# Master.net
KiCad netlist of a schematic drawn in EAGLE
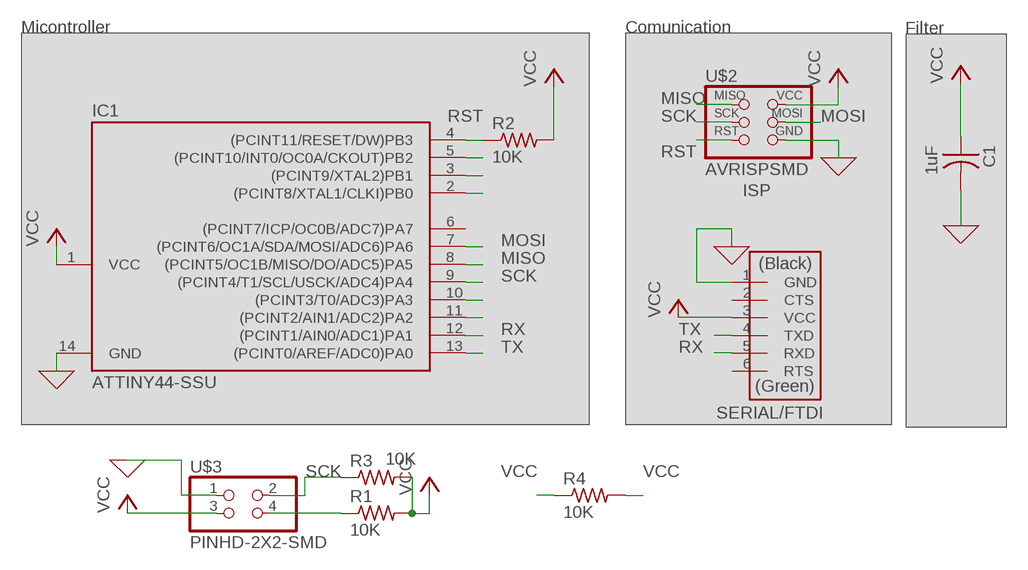
[diagram p0: schematic, sheet 1]

(export (version "E")
  (design (tool "Eeschema 10.0.6"))
  (components
    (comp (ref "C1")
      (value "1uF")
      (footprint "eagle-import:C1206FAB")
      (libsource (lib "eagle-import") (part "CAP-US1206FAB"))
    )
    (comp (ref "IC1")
      (value "ATTINY44-SSU")
      (footprint "eagle-import:SOIC14")
      (libsource (lib "eagle-import") (part "ATTINY44-SSU"))
    )
    (comp (ref "R1")
      (value "10K")
      (footprint "eagle-import:R1206FAB")
      (libsource (lib "eagle-import") (part "RES-US1206FAB"))
    )
    (comp (ref "R2")
      (value "10K")
      (footprint "eagle-import:R1206FAB")
      (libsource (lib "eagle-import") (part "RES-US1206FAB"))
    )
    (comp (ref "R3")
      (value "10K")
      (footprint "eagle-import:R1206FAB")
      (libsource (lib "eagle-import") (part "RES-US1206FAB"))
    )
    (comp (ref "R4")
      (value "10K")
      (footprint "eagle-import:R1206FAB")
      (libsource (lib "eagle-import") (part "RES-US1206FAB"))
    )
    (comp (ref "U$1")
      (value "FTDI-SMD-HEADER")
      (footprint "eagle-import:1X06SMD")
      (libsource (lib "eagle-import") (part "FTDI-SMD-HEADER"))
    )
    (comp (ref "U$2")
      (value "AVRISPSMD")
      (footprint "eagle-import:2X03SMD")
      (libsource (lib "eagle-import") (part "AVRISPSMD"))
    )
    (comp (ref "U$3")
      (value "PINHD-2X2-SMD")
      (footprint "eagle-import:2X02SMD")
      (libsource (lib "eagle-import") (part "PINHD-2X2-SMD"))
    )
  )
  (nets
    (net (code "1") (name "/MISO") (class "Default")
      (node (ref "IC1") (pin "8") (pinfunction "(PCINT5/OC1B/MISO/DO/ADC5)PA5_8") (pintype "bidirectional"))
      (node (ref "U$2") (pin "1") (pinfunction "MISO_1") (pintype "passive"))
    )
    (net (code "2") (name "/MOSI") (class "Default")
      (node (ref "IC1") (pin "7") (pinfunction "(PCINT6/OC1A/SDA/MOSI/ADC6)PA6_7") (pintype "bidirectional"))
      (node (ref "R1") (pin "1") (pinfunction "1_1") (pintype "passive"))
      (node (ref "U$2") (pin "4") (pinfunction "MOSI_4") (pintype "passive"))
      (node (ref "U$3") (pin "4") (pinfunction "4_4") (pintype "passive"))
    )
    (net (code "3") (name "/RST") (class "Default")
      (node (ref "IC1") (pin "4") (pinfunction "(PCINT11/RESET/DW)PB3_4") (pintype "bidirectional"))
      (node (ref "R2") (pin "1") (pinfunction "1_1") (pintype "passive"))
      (node (ref "U$2") (pin "5") (pinfunction "RST_5") (pintype "passive"))
    )
    (net (code "4") (name "/RX") (class "Default")
      (node (ref "IC1") (pin "12") (pinfunction "(PCINT1/AIN0/ADC1)PA1_12") (pintype "bidirectional"))
      (node (ref "U$1") (pin "5") (pinfunction "RXD_5") (pintype "bidirectional"))
    )
    (net (code "5") (name "/SCK") (class "Default")
      (node (ref "IC1") (pin "9") (pinfunction "(PCINT4/T1/SCL/USCK/ADC4)PA4_9") (pintype "bidirectional"))
      (node (ref "R3") (pin "1") (pinfunction "1_1") (pintype "passive"))
      (node (ref "U$2") (pin "3") (pinfunction "SCK_3") (pintype "passive"))
      (node (ref "U$3") (pin "2") (pinfunction "2_2") (pintype "passive"))
    )
    (net (code "6") (name "/TX") (class "Default")
      (node (ref "IC1") (pin "13") (pinfunction "(PCINT0/AREF/ADC0)PA0_13") (pintype "bidirectional"))
      (node (ref "U$1") (pin "4") (pinfunction "TXD_4") (pintype "bidirectional"))
    )
    (net (code "7") (name "GND") (class "Default")
      (node (ref "C1") (pin "2") (pinfunction "2_2") (pintype "passive"))
      (node (ref "IC1") (pin "14") (pinfunction "GND_14") (pintype "power_in"))
      (node (ref "U$1") (pin "1") (pinfunction "GND_1") (pintype "bidirectional"))
      (node (ref "U$2") (pin "6") (pinfunction "GND_6") (pintype "passive"))
      (node (ref "U$3") (pin "1") (pinfunction "1_1") (pintype "passive"))
    )
    (net (code "8") (name "VCC") (class "Default")
      (node (ref "C1") (pin "1") (pinfunction "1_1") (pintype "passive"))
      (node (ref "IC1") (pin "1") (pinfunction "VCC_1") (pintype "power_in"))
      (node (ref "R1") (pin "2") (pinfunction "2_2") (pintype "passive"))
      (node (ref "R2") (pin "2") (pinfunction "2_2") (pintype "passive"))
      (node (ref "R3") (pin "2") (pinfunction "2_2") (pintype "passive"))
      (node (ref "R4") (pin "1") (pinfunction "1_1") (pintype "passive"))
      (node (ref "R4") (pin "2") (pinfunction "2_2") (pintype "passive"))
      (node (ref "U$1") (pin "3") (pinfunction "VCC_3") (pintype "bidirectional"))
      (node (ref "U$2") (pin "2") (pinfunction "VCC_2") (pintype "passive"))
      (node (ref "U$3") (pin "3") (pinfunction "3_3") (pintype "passive"))
    )
    (net (code "9") (name "unconnected-(IC1-(PCINT2{slash}AIN1{slash}ADC2)PA2-Pad11)") (class "Default")
      (node (ref "IC1") (pin "11") (pinfunction "(PCINT2/AIN1/ADC2)PA2_11") (pintype "bidirectional"))
    )
    (net (code "10") (name "unconnected-(IC1-(PCINT3{slash}T0{slash}ADC3)PA3-Pad10)") (class "Default")
      (node (ref "IC1") (pin "10") (pinfunction "(PCINT3/T0/ADC3)PA3_10") (pintype "bidirectional"))
    )
    (net (code "11") (name "unconnected-(IC1-(PCINT7{slash}ICP{slash}OC0B{slash}ADC7)PA7-Pad6)") (class "Default")
      (node (ref "IC1") (pin "6") (pinfunction "(PCINT7/ICP/OC0B/ADC7)PA7_6") (pintype "bidirectional"))
    )
    (net (code "12") (name "unconnected-(IC1-(PCINT8{slash}XTAL1{slash}CLKI)PB0-Pad2)") (class "Default")
      (node (ref "IC1") (pin "2") (pinfunction "(PCINT8/XTAL1/CLKI)PB0_2") (pintype "bidirectional"))
    )
    (net (code "13") (name "unconnected-(IC1-(PCINT9{slash}XTAL2)PB1-Pad3)") (class "Default")
      (node (ref "IC1") (pin "3") (pinfunction "(PCINT9/XTAL2)PB1_3") (pintype "bidirectional"))
    )
    (net (code "14") (name "unconnected-(IC1-(PCINT10{slash}INT0{slash}OC0A{slash}CKOUT)PB2-Pad5)") (class "Default")
      (node (ref "IC1") (pin "5") (pinfunction "(PCINT10/INT0/OC0A/CKOUT)PB2_5") (pintype "bidirectional"))
    )
    (net (code "15") (name "unconnected-(U$1-CTS-Pad2)") (class "Default")
      (node (ref "U$1") (pin "2") (pinfunction "CTS_2") (pintype "bidirectional"))
    )
    (net (code "16") (name "unconnected-(U$1-RTS-Pad6)") (class "Default")
      (node (ref "U$1") (pin "6") (pinfunction "RTS_6") (pintype "bidirectional"))
    )
  )
)
